# TopPanelV5.net
KiCad netlist of a schematic drawn in EAGLE
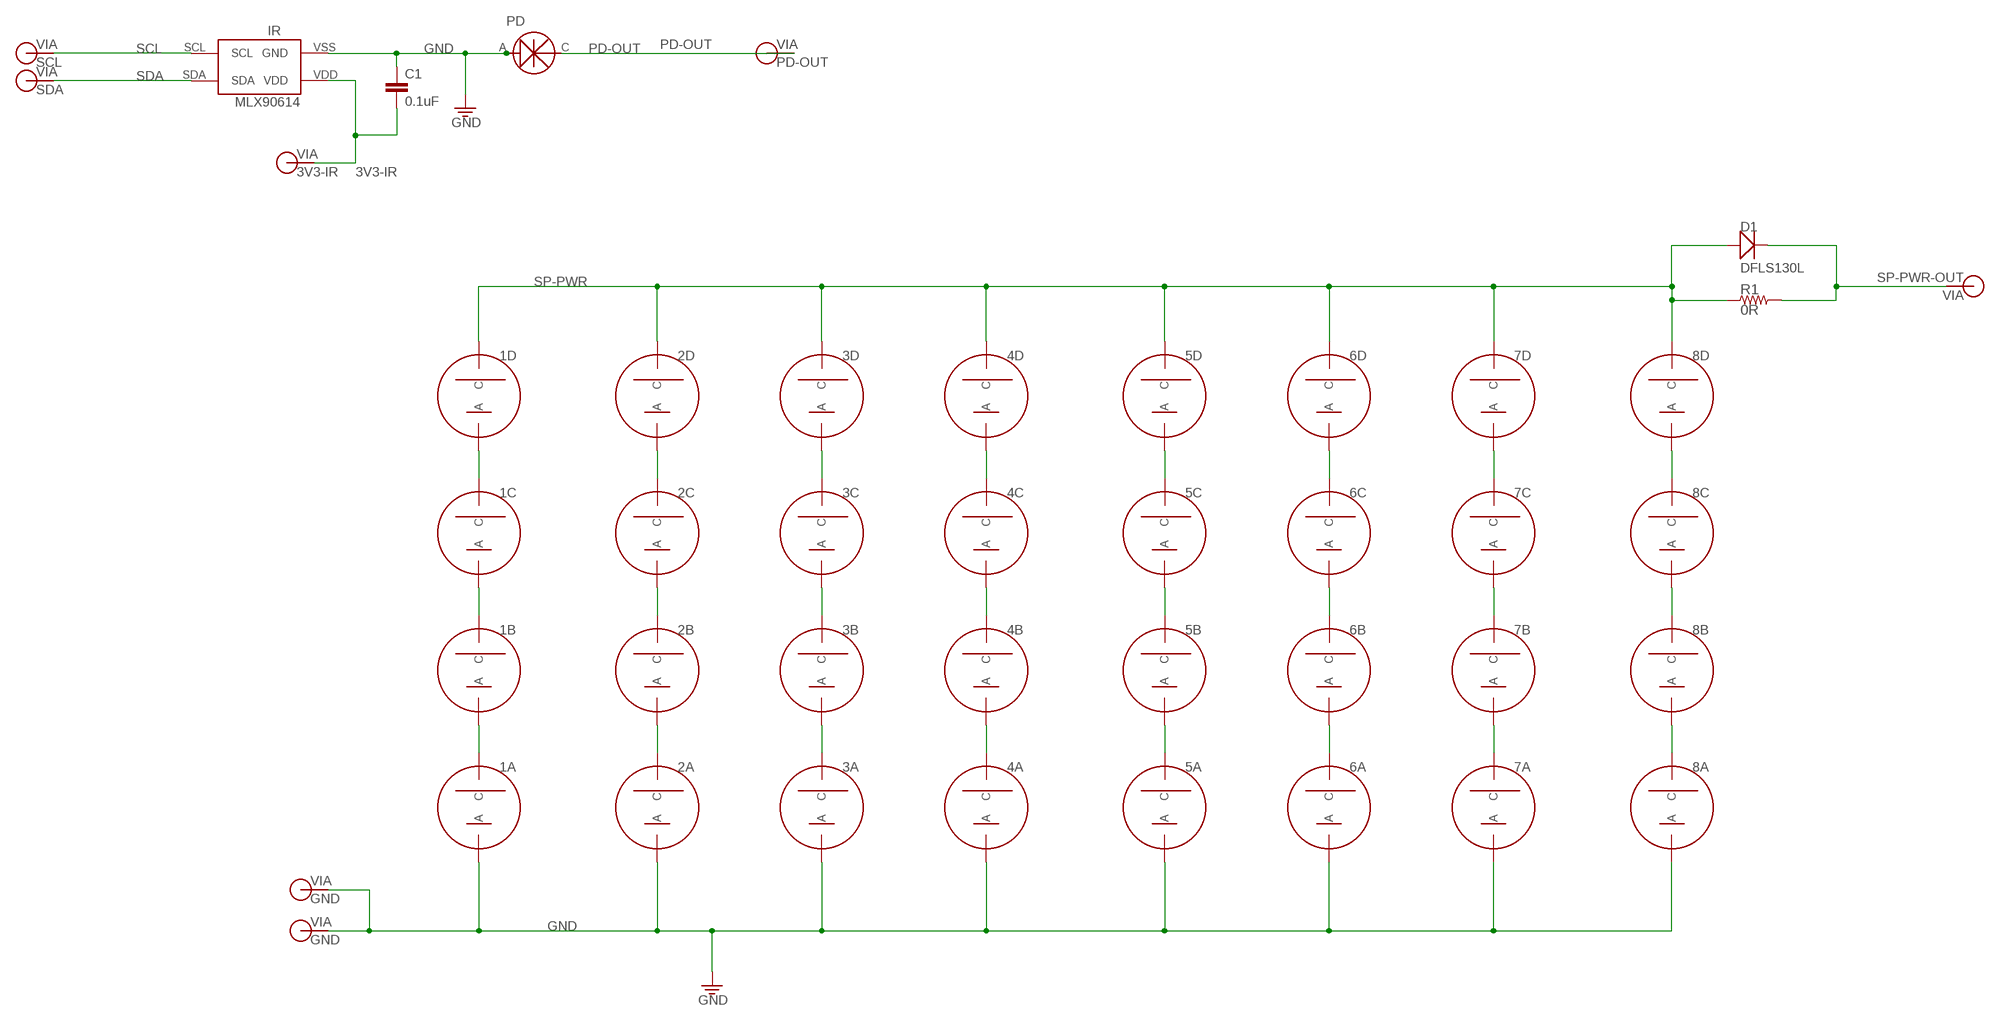
[diagram p0: schematic, sheet 1]

(export (version "E")
  (design (tool "Eeschema 10.0.6"))
  (components
    (comp (ref "1A")
      (value "SOLARCELLV3")
      (footprint "eagle-import:TRISOLX-V3")
      (libsource (lib "eagle-import") (part "SOLARCELLV3"))
    )
    (comp (ref "1B")
      (value "SOLARCELLV3")
      (footprint "eagle-import:TRISOLX-V3")
      (libsource (lib "eagle-import") (part "SOLARCELLV3"))
    )
    (comp (ref "1C")
      (value "SOLARCELLV3")
      (footprint "eagle-import:TRISOLX-V3")
      (libsource (lib "eagle-import") (part "SOLARCELLV3"))
    )
    (comp (ref "1D")
      (value "SOLARCELLV3")
      (footprint "eagle-import:TRISOLX-V3")
      (libsource (lib "eagle-import") (part "SOLARCELLV3"))
    )
    (comp (ref "2A")
      (value "SOLARCELLV3")
      (footprint "eagle-import:TRISOLX-V3")
      (libsource (lib "eagle-import") (part "SOLARCELLV3"))
    )
    (comp (ref "2B")
      (value "SOLARCELLV3")
      (footprint "eagle-import:TRISOLX-V3")
      (libsource (lib "eagle-import") (part "SOLARCELLV3"))
    )
    (comp (ref "2C")
      (value "SOLARCELLV3")
      (footprint "eagle-import:TRISOLX-V3")
      (libsource (lib "eagle-import") (part "SOLARCELLV3"))
    )
    (comp (ref "2D")
      (value "SOLARCELLV3")
      (footprint "eagle-import:TRISOLX-V3")
      (libsource (lib "eagle-import") (part "SOLARCELLV3"))
    )
    (comp (ref "3A")
      (value "SOLARCELLV3")
      (footprint "eagle-import:TRISOLX-V3")
      (libsource (lib "eagle-import") (part "SOLARCELLV3"))
    )
    (comp (ref "3B")
      (value "SOLARCELLV3")
      (footprint "eagle-import:TRISOLX-V3")
      (libsource (lib "eagle-import") (part "SOLARCELLV3"))
    )
    (comp (ref "3C")
      (value "SOLARCELLV3")
      (footprint "eagle-import:TRISOLX-V3")
      (libsource (lib "eagle-import") (part "SOLARCELLV3"))
    )
    (comp (ref "3D")
      (value "SOLARCELLV3")
      (footprint "eagle-import:TRISOLX-V3")
      (libsource (lib "eagle-import") (part "SOLARCELLV3"))
    )
    (comp (ref "4A")
      (value "SOLARCELLV3")
      (footprint "eagle-import:TRISOLX-V3")
      (libsource (lib "eagle-import") (part "SOLARCELLV3"))
    )
    (comp (ref "4B")
      (value "SOLARCELLV3")
      (footprint "eagle-import:TRISOLX-V3")
      (libsource (lib "eagle-import") (part "SOLARCELLV3"))
    )
    (comp (ref "4C")
      (value "SOLARCELLV3")
      (footprint "eagle-import:TRISOLX-V3")
      (libsource (lib "eagle-import") (part "SOLARCELLV3"))
    )
    (comp (ref "4D")
      (value "SOLARCELLV3")
      (footprint "eagle-import:TRISOLX-V3")
      (libsource (lib "eagle-import") (part "SOLARCELLV3"))
    )
    (comp (ref "5A")
      (value "SOLARCELLV3")
      (footprint "eagle-import:TRISOLX-V3")
      (libsource (lib "eagle-import") (part "SOLARCELLV3"))
    )
    (comp (ref "5B")
      (value "SOLARCELLV3")
      (footprint "eagle-import:TRISOLX-V3")
      (libsource (lib "eagle-import") (part "SOLARCELLV3"))
    )
    (comp (ref "5C")
      (value "SOLARCELLV3")
      (footprint "eagle-import:TRISOLX-V3")
      (libsource (lib "eagle-import") (part "SOLARCELLV3"))
    )
    (comp (ref "5D")
      (value "SOLARCELLV3")
      (footprint "eagle-import:TRISOLX-V3")
      (libsource (lib "eagle-import") (part "SOLARCELLV3"))
    )
    (comp (ref "6A")
      (value "SOLARCELLV3")
      (footprint "eagle-import:TRISOLX-V3")
      (libsource (lib "eagle-import") (part "SOLARCELLV3"))
    )
    (comp (ref "6B")
      (value "SOLARCELLV3")
      (footprint "eagle-import:TRISOLX-V3")
      (libsource (lib "eagle-import") (part "SOLARCELLV3"))
    )
    (comp (ref "6C")
      (value "SOLARCELLV3")
      (footprint "eagle-import:TRISOLX-V3")
      (libsource (lib "eagle-import") (part "SOLARCELLV3"))
    )
    (comp (ref "6D")
      (value "SOLARCELLV3")
      (footprint "eagle-import:TRISOLX-V3")
      (libsource (lib "eagle-import") (part "SOLARCELLV3"))
    )
    (comp (ref "7A")
      (value "SOLARCELLV3")
      (footprint "eagle-import:TRISOLX-V3")
      (libsource (lib "eagle-import") (part "SOLARCELLV3"))
    )
    (comp (ref "7B")
      (value "SOLARCELLV3")
      (footprint "eagle-import:TRISOLX-V3")
      (libsource (lib "eagle-import") (part "SOLARCELLV3"))
    )
    (comp (ref "7C")
      (value "SOLARCELLV3")
      (footprint "eagle-import:TRISOLX-V3")
      (libsource (lib "eagle-import") (part "SOLARCELLV3"))
    )
    (comp (ref "7D")
      (value "SOLARCELLV3")
      (footprint "eagle-import:TRISOLX-V3")
      (libsource (lib "eagle-import") (part "SOLARCELLV3"))
    )
    (comp (ref "8A")
      (value "SOLARCELLV3")
      (footprint "eagle-import:TRISOLX-V3")
      (libsource (lib "eagle-import") (part "SOLARCELLV3"))
    )
    (comp (ref "8B")
      (value "SOLARCELLV3")
      (footprint "eagle-import:TRISOLX-V3")
      (libsource (lib "eagle-import") (part "SOLARCELLV3"))
    )
    (comp (ref "8C")
      (value "SOLARCELLV3")
      (footprint "eagle-import:TRISOLX-V3")
      (libsource (lib "eagle-import") (part "SOLARCELLV3"))
    )
    (comp (ref "8D")
      (value "SOLARCELLV3")
      (footprint "eagle-import:TRISOLX-V3")
      (libsource (lib "eagle-import") (part "SOLARCELLV3"))
    )
    (comp (ref "C1")
      (value "0.1uF")
      (footprint "eagle-import:0805")
      (libsource (lib "eagle-import") (part "CAP0805"))
    )
    (comp (ref "D1")
      (value "DFLS130L")
      (footprint "eagle-import:PWRDI-123")
      (libsource (lib "eagle-import") (part "DFLS130L"))
    )
    (comp (ref "IR")
      (value "MXL90614")
      (footprint "eagle-import:MXL90620")
      (libsource (lib "eagle-import") (part "MXL90614"))
    )
    (comp (ref "PD")
      (value "TEMD6200")
      (footprint "eagle-import:TEMD6200")
      (libsource (lib "eagle-import") (part "TEMD6200"))
    )
    (comp (ref "R1")
      (value "0R")
      (footprint "eagle-import:1210")
      (libsource (lib "eagle-import") (part "RES1210"))
    )
    (comp (ref "SCL")
      (value "SCL")
      (footprint "eagle-import:VIA-60MIL")
      (libsource (lib "eagle-import") (part "VIA-60MIL"))
    )
    (comp (ref "SDA")
      (value "SDA")
      (footprint "eagle-import:VIA-60MIL")
      (libsource (lib "eagle-import") (part "VIA-60MIL"))
    )
    (comp (ref "V1")
      (value "SP-PWR-OUT")
      (footprint "eagle-import:VIA-60MIL")
      (libsource (lib "eagle-import") (part "VIA-60MIL"))
    )
    (comp (ref "V2")
      (value "GND")
      (footprint "eagle-import:VIA-60MIL")
      (libsource (lib "eagle-import") (part "VIA-60MIL"))
    )
    (comp (ref "V3")
      (value "3V3-IR")
      (footprint "eagle-import:VIA-60MIL")
      (libsource (lib "eagle-import") (part "VIA-60MIL"))
    )
    (comp (ref "V4")
      (value "GND")
      (footprint "eagle-import:VIA-60MIL")
      (libsource (lib "eagle-import") (part "VIA-60MIL"))
    )
    (comp (ref "V6")
      (value "PD-OUT")
      (footprint "eagle-import:VIA-60MIL")
      (libsource (lib "eagle-import") (part "VIA-60MIL"))
    )
  )
  (nets
    (net (code "1") (name "/3V3-IR") (class "Default")
      (node (ref "C1") (pin "2") (pinfunction "2_2") (pintype "passive"))
      (node (ref "IR") (pin "VDD") (pinfunction "VDD_VDD") (pintype "bidirectional"))
      (node (ref "V3") (pin "P$1") (pinfunction "P$1_P$1") (pintype "bidirectional"))
    )
    (net (code "2") (name "/PD-OUT") (class "Default")
      (node (ref "PD") (pin "C") (pinfunction "C_C") (pintype "bidirectional"))
      (node (ref "V6") (pin "P$1") (pinfunction "P$1_P$1") (pintype "bidirectional"))
    )
    (net (code "3") (name "/SCL") (class "Default")
      (node (ref "IR") (pin "SCL") (pinfunction "SCL_SCL") (pintype "bidirectional"))
      (node (ref "SCL") (pin "P$1") (pinfunction "P$1_P$1") (pintype "bidirectional"))
    )
    (net (code "4") (name "/SDA") (class "Default")
      (node (ref "IR") (pin "SDA") (pinfunction "SDA_SDA") (pintype "bidirectional"))
      (node (ref "SDA") (pin "P$1") (pinfunction "P$1_P$1") (pintype "bidirectional"))
    )
    (net (code "5") (name "/SP-PWR") (class "Default")
      (node (ref "1D") (pin "CATHODE") (pinfunction "C_CATHODE") (pintype "bidirectional"))
      (node (ref "2D") (pin "CATHODE") (pinfunction "C_CATHODE") (pintype "bidirectional"))
      (node (ref "3D") (pin "CATHODE") (pinfunction "C_CATHODE") (pintype "bidirectional"))
      (node (ref "4D") (pin "CATHODE") (pinfunction "C_CATHODE") (pintype "bidirectional"))
      (node (ref "5D") (pin "CATHODE") (pinfunction "C_CATHODE") (pintype "bidirectional"))
      (node (ref "6D") (pin "CATHODE") (pinfunction "C_CATHODE") (pintype "bidirectional"))
      (node (ref "7D") (pin "CATHODE") (pinfunction "C_CATHODE") (pintype "bidirectional"))
      (node (ref "8D") (pin "CATHODE") (pinfunction "C_CATHODE") (pintype "bidirectional"))
      (node (ref "D1") (pin "A") (pinfunction "A_A") (pintype "bidirectional"))
      (node (ref "R1") (pin "P$1") (pinfunction "1_P$1") (pintype "passive"))
    )
    (net (code "6") (name "GND") (class "Default")
      (node (ref "1A") (pin "ANODE") (pinfunction "A_ANODE") (pintype "bidirectional"))
      (node (ref "2A") (pin "ANODE") (pinfunction "A_ANODE") (pintype "bidirectional"))
      (node (ref "3A") (pin "ANODE") (pinfunction "A_ANODE") (pintype "bidirectional"))
      (node (ref "4A") (pin "ANODE") (pinfunction "A_ANODE") (pintype "bidirectional"))
      (node (ref "5A") (pin "ANODE") (pinfunction "A_ANODE") (pintype "bidirectional"))
      (node (ref "6A") (pin "ANODE") (pinfunction "A_ANODE") (pintype "bidirectional"))
      (node (ref "7A") (pin "ANODE") (pinfunction "A_ANODE") (pintype "bidirectional"))
      (node (ref "8A") (pin "ANODE") (pinfunction "A_ANODE") (pintype "bidirectional"))
      (node (ref "C1") (pin "1") (pinfunction "1_1") (pintype "passive"))
      (node (ref "IR") (pin "VSS") (pinfunction "GND_VSS") (pintype "bidirectional"))
      (node (ref "PD") (pin "A") (pinfunction "A_A") (pintype "bidirectional"))
      (node (ref "V2") (pin "P$1") (pinfunction "P$1_P$1") (pintype "bidirectional"))
      (node (ref "V4") (pin "P$1") (pinfunction "P$1_P$1") (pintype "bidirectional"))
    )
    (net (code "7") (name "Net-(1A-C)") (class "Default")
      (node (ref "1A") (pin "CATHODE") (pinfunction "C_CATHODE") (pintype "bidirectional"))
      (node (ref "1B") (pin "ANODE") (pinfunction "A_ANODE") (pintype "bidirectional"))
    )
    (net (code "8") (name "Net-(1B-C)") (class "Default")
      (node (ref "1B") (pin "CATHODE") (pinfunction "C_CATHODE") (pintype "bidirectional"))
      (node (ref "1C") (pin "ANODE") (pinfunction "A_ANODE") (pintype "bidirectional"))
    )
    (net (code "9") (name "Net-(1C-C)") (class "Default")
      (node (ref "1C") (pin "CATHODE") (pinfunction "C_CATHODE") (pintype "bidirectional"))
      (node (ref "1D") (pin "ANODE") (pinfunction "A_ANODE") (pintype "bidirectional"))
    )
    (net (code "10") (name "Net-(2A-C)") (class "Default")
      (node (ref "2A") (pin "CATHODE") (pinfunction "C_CATHODE") (pintype "bidirectional"))
      (node (ref "2B") (pin "ANODE") (pinfunction "A_ANODE") (pintype "bidirectional"))
    )
    (net (code "11") (name "Net-(2B-C)") (class "Default")
      (node (ref "2B") (pin "CATHODE") (pinfunction "C_CATHODE") (pintype "bidirectional"))
      (node (ref "2C") (pin "ANODE") (pinfunction "A_ANODE") (pintype "bidirectional"))
    )
    (net (code "12") (name "Net-(2C-C)") (class "Default")
      (node (ref "2C") (pin "CATHODE") (pinfunction "C_CATHODE") (pintype "bidirectional"))
      (node (ref "2D") (pin "ANODE") (pinfunction "A_ANODE") (pintype "bidirectional"))
    )
    (net (code "13") (name "Net-(3A-C)") (class "Default")
      (node (ref "3A") (pin "CATHODE") (pinfunction "C_CATHODE") (pintype "bidirectional"))
      (node (ref "3B") (pin "ANODE") (pinfunction "A_ANODE") (pintype "bidirectional"))
    )
    (net (code "14") (name "Net-(3B-C)") (class "Default")
      (node (ref "3B") (pin "CATHODE") (pinfunction "C_CATHODE") (pintype "bidirectional"))
      (node (ref "3C") (pin "ANODE") (pinfunction "A_ANODE") (pintype "bidirectional"))
    )
    (net (code "15") (name "Net-(3C-C)") (class "Default")
      (node (ref "3C") (pin "CATHODE") (pinfunction "C_CATHODE") (pintype "bidirectional"))
      (node (ref "3D") (pin "ANODE") (pinfunction "A_ANODE") (pintype "bidirectional"))
    )
    (net (code "16") (name "Net-(4A-C)") (class "Default")
      (node (ref "4A") (pin "CATHODE") (pinfunction "C_CATHODE") (pintype "bidirectional"))
      (node (ref "4B") (pin "ANODE") (pinfunction "A_ANODE") (pintype "bidirectional"))
    )
    (net (code "17") (name "Net-(4B-C)") (class "Default")
      (node (ref "4B") (pin "CATHODE") (pinfunction "C_CATHODE") (pintype "bidirectional"))
      (node (ref "4C") (pin "ANODE") (pinfunction "A_ANODE") (pintype "bidirectional"))
    )
    (net (code "18") (name "Net-(4C-C)") (class "Default")
      (node (ref "4C") (pin "CATHODE") (pinfunction "C_CATHODE") (pintype "bidirectional"))
      (node (ref "4D") (pin "ANODE") (pinfunction "A_ANODE") (pintype "bidirectional"))
    )
    (net (code "19") (name "Net-(5A-C)") (class "Default")
      (node (ref "5A") (pin "CATHODE") (pinfunction "C_CATHODE") (pintype "bidirectional"))
      (node (ref "5B") (pin "ANODE") (pinfunction "A_ANODE") (pintype "bidirectional"))
    )
    (net (code "20") (name "Net-(5B-C)") (class "Default")
      (node (ref "5B") (pin "CATHODE") (pinfunction "C_CATHODE") (pintype "bidirectional"))
      (node (ref "5C") (pin "ANODE") (pinfunction "A_ANODE") (pintype "bidirectional"))
    )
    (net (code "21") (name "Net-(5C-C)") (class "Default")
      (node (ref "5C") (pin "CATHODE") (pinfunction "C_CATHODE") (pintype "bidirectional"))
      (node (ref "5D") (pin "ANODE") (pinfunction "A_ANODE") (pintype "bidirectional"))
    )
    (net (code "22") (name "Net-(6A-C)") (class "Default")
      (node (ref "6A") (pin "CATHODE") (pinfunction "C_CATHODE") (pintype "bidirectional"))
      (node (ref "6B") (pin "ANODE") (pinfunction "A_ANODE") (pintype "bidirectional"))
    )
    (net (code "23") (name "Net-(6B-C)") (class "Default")
      (node (ref "6B") (pin "CATHODE") (pinfunction "C_CATHODE") (pintype "bidirectional"))
      (node (ref "6C") (pin "ANODE") (pinfunction "A_ANODE") (pintype "bidirectional"))
    )
    (net (code "24") (name "Net-(6C-C)") (class "Default")
      (node (ref "6C") (pin "CATHODE") (pinfunction "C_CATHODE") (pintype "bidirectional"))
      (node (ref "6D") (pin "ANODE") (pinfunction "A_ANODE") (pintype "bidirectional"))
    )
    (net (code "25") (name "Net-(7A-C)") (class "Default")
      (node (ref "7A") (pin "CATHODE") (pinfunction "C_CATHODE") (pintype "bidirectional"))
      (node (ref "7B") (pin "ANODE") (pinfunction "A_ANODE") (pintype "bidirectional"))
    )
    (net (code "26") (name "Net-(7B-C)") (class "Default")
      (node (ref "7B") (pin "CATHODE") (pinfunction "C_CATHODE") (pintype "bidirectional"))
      (node (ref "7C") (pin "ANODE") (pinfunction "A_ANODE") (pintype "bidirectional"))
    )
    (net (code "27") (name "Net-(7C-C)") (class "Default")
      (node (ref "7C") (pin "CATHODE") (pinfunction "C_CATHODE") (pintype "bidirectional"))
      (node (ref "7D") (pin "ANODE") (pinfunction "A_ANODE") (pintype "bidirectional"))
    )
    (net (code "28") (name "Net-(8A-C)") (class "Default")
      (node (ref "8A") (pin "CATHODE") (pinfunction "C_CATHODE") (pintype "bidirectional"))
      (node (ref "8B") (pin "ANODE") (pinfunction "A_ANODE") (pintype "bidirectional"))
    )
    (net (code "29") (name "Net-(8B-C)") (class "Default")
      (node (ref "8B") (pin "CATHODE") (pinfunction "C_CATHODE") (pintype "bidirectional"))
      (node (ref "8C") (pin "ANODE") (pinfunction "A_ANODE") (pintype "bidirectional"))
    )
    (net (code "30") (name "Net-(8C-C)") (class "Default")
      (node (ref "8C") (pin "CATHODE") (pinfunction "C_CATHODE") (pintype "bidirectional"))
      (node (ref "8D") (pin "ANODE") (pinfunction "A_ANODE") (pintype "bidirectional"))
    )
    (net (code "31") (name "Net-(R1-2)") (class "Default")
      (node (ref "D1") (pin "C") (pinfunction "C_C") (pintype "bidirectional"))
      (node (ref "R1") (pin "P$2") (pinfunction "2_P$2") (pintype "passive"))
      (node (ref "V1") (pin "P$1") (pinfunction "P$1_P$1") (pintype "bidirectional"))
    )
  )
)
